# AMU-S05-V00-IsolatedCAN2.net
KiCad netlist of a schematic drawn in Altium Designer
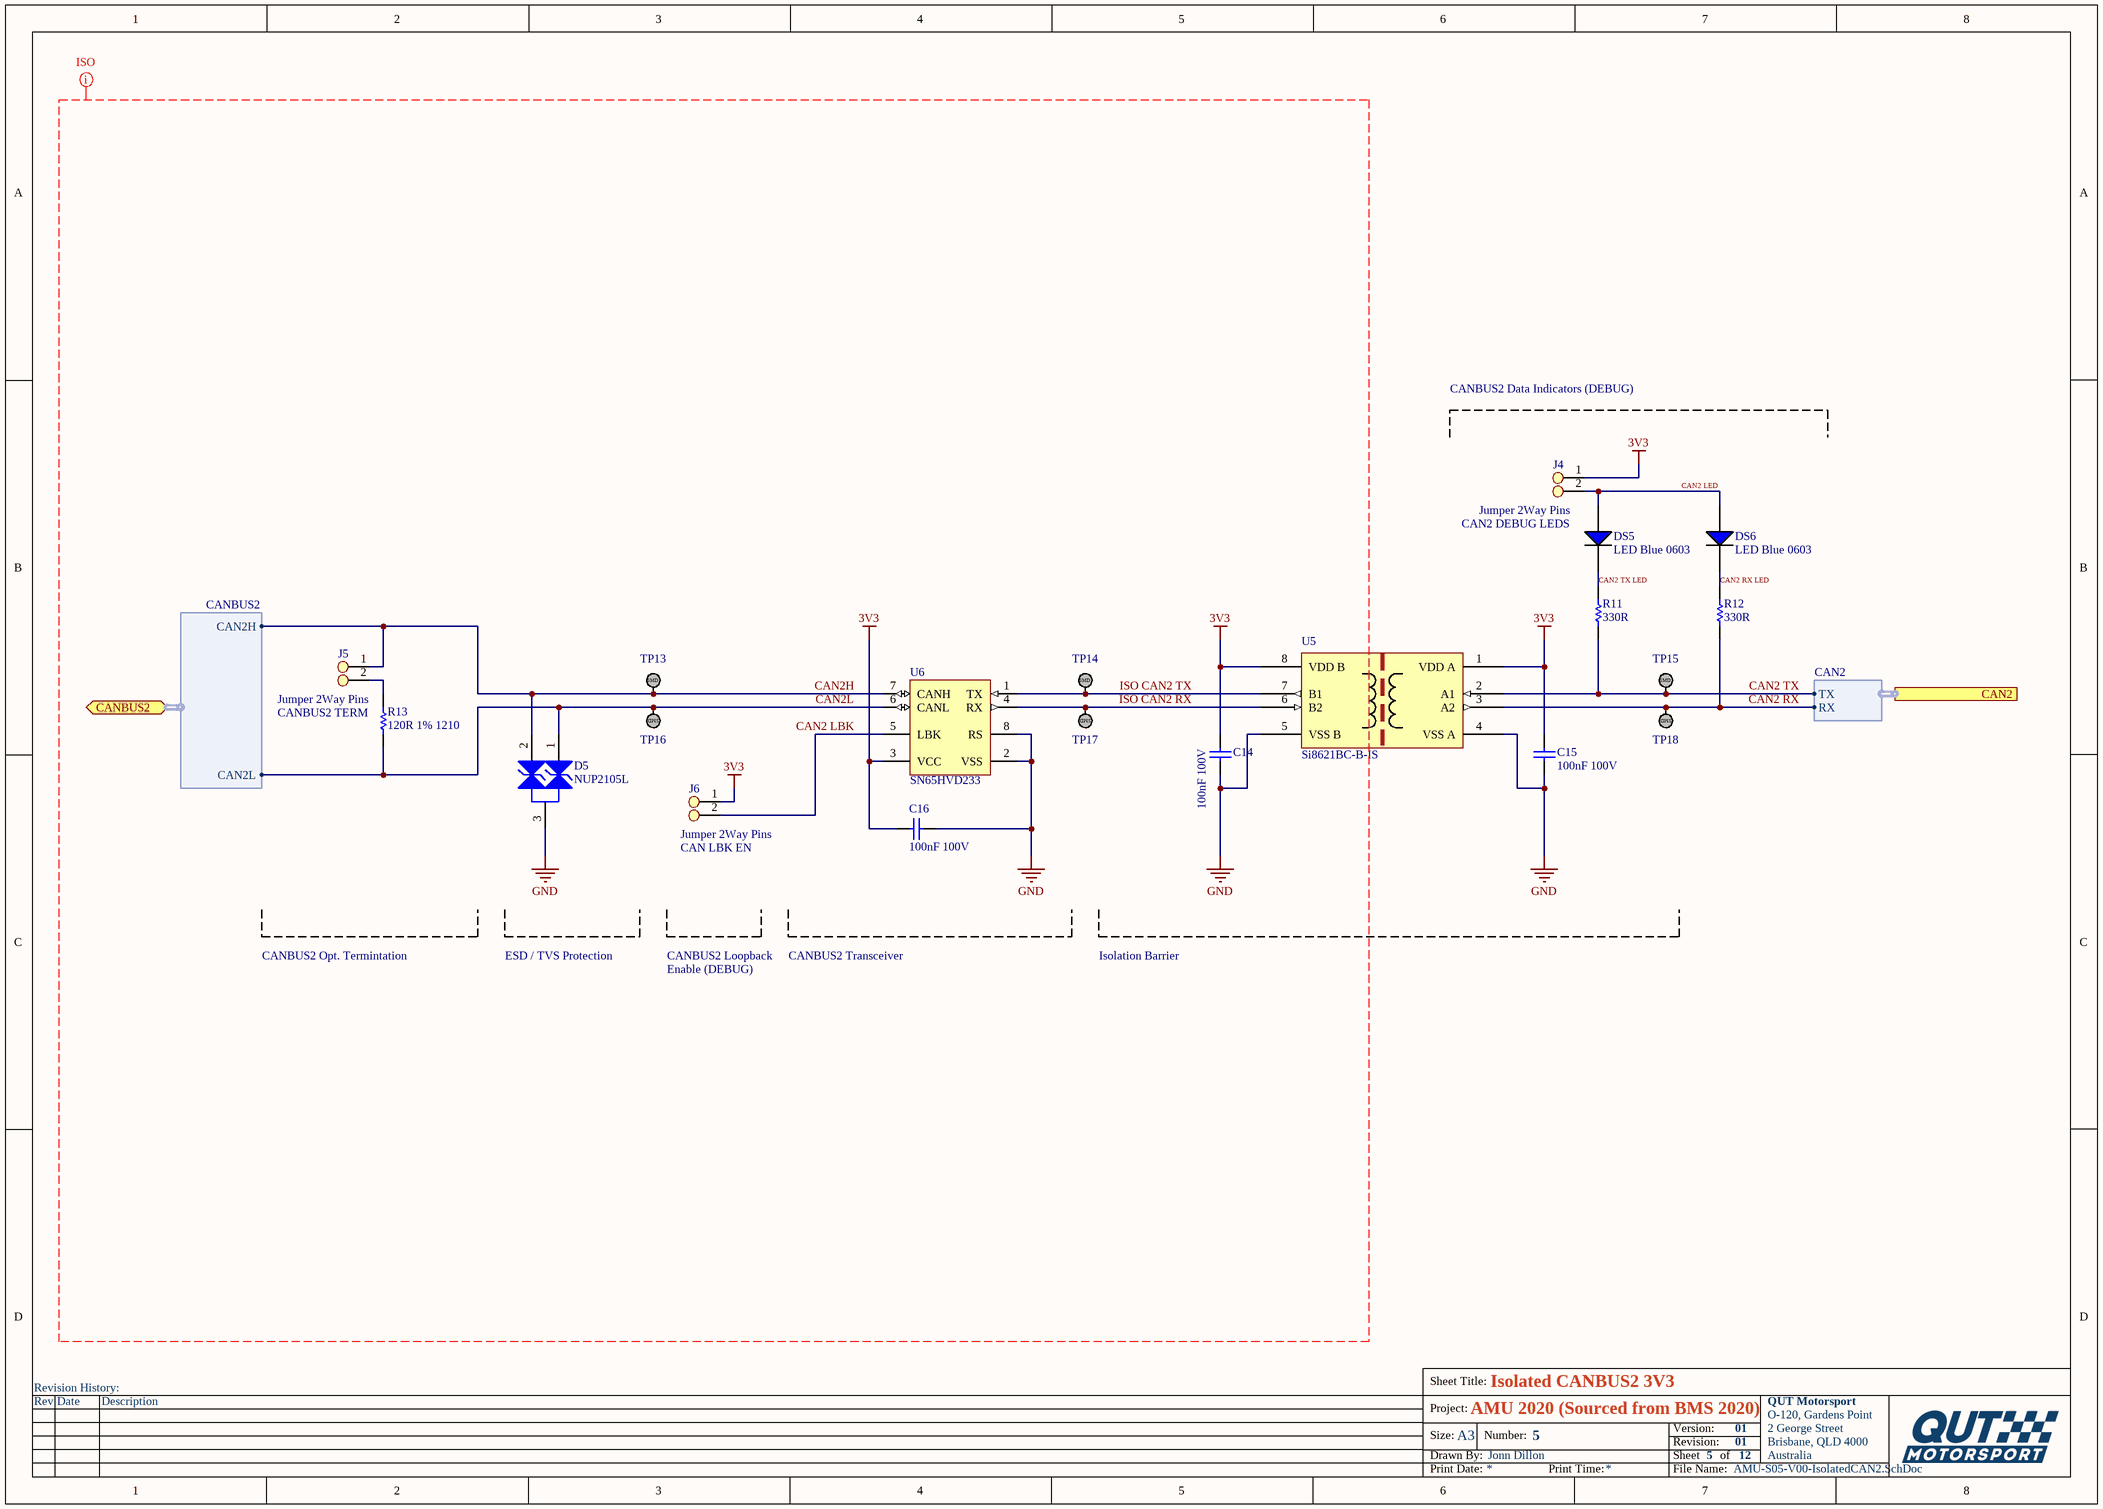
[diagram p0: AMU-S05-V00-IsolatedCAN2.SchDoc]

(export (version "E")
  (design (tool "Eeschema 10.0.6"))
  (components
    (comp (ref "C14")
      (value "100nF 100V")
      (footprint "Cap_Ceramic_0603")
      (description "Capacitor, Ceramic, SMD, 100nF, 100V, 5%, X7R, 0603")
      (libsource (lib "StandardCapacitors") (part "100nF 100V 5% X7R 0603"))
    )
    (comp (ref "C15")
      (value "100nF 100V")
      (footprint "Cap_Ceramic_0603")
      (description "Capacitor, Ceramic, SMD, 100nF, 100V, 5%, X7R, 0603")
      (libsource (lib "StandardCapacitors") (part "100nF 100V 5% X7R 0603"))
    )
    (comp (ref "C16")
      (value "100nF 100V")
      (footprint "Cap_Ceramic_0603")
      (description "Capacitor, Ceramic, SMD, 100nF, 100V, 5%, X7R, 0603")
      (libsource (lib "StandardCapacitors") (part "100nF 100V 5% X7R 0603"))
    )
    (comp (ref "D5")
      (value "NUP2105L")
      (footprint "NUP2105L")
      (libsource (lib "QUTMS_CANLibrary") (part "NUP2105L"))
    )
    (comp (ref "DS5")
      (value "LED Blue 0603")
      (footprint "LED BLUE 0603")
      (libsource (lib "QUTMS_LEDLibrary") (part "LED BLUE 0603"))
    )
    (comp (ref "DS6")
      (value "LED Blue 0603")
      (footprint "LED BLUE 0603")
      (libsource (lib "QUTMS_LEDLibrary") (part "LED BLUE 0603"))
    )
    (comp (ref "J4")
      (value "Jumper 2Way Pins")
      (footprint "Jumper_2Way_Pin")
      (description "Jumper 2Way Side Pins")
      (libsource (lib "QUTMS_JumperLibrary") (part "Jumper 2Way Side Pins"))
    )
    (comp (ref "J5")
      (value "Jumper 2Way Pins")
      (footprint "Jumper_2Way_Pin")
      (description "Jumper 2Way Side Pins")
      (libsource (lib "QUTMS_JumperLibrary") (part "Jumper 2Way Side Pins"))
    )
    (comp (ref "J6")
      (value "Jumper 2Way Pins")
      (footprint "Jumper_2Way_Pin")
      (description "Jumper 2Way Side Pins")
      (libsource (lib "QUTMS_JumperLibrary") (part "Jumper 2Way Side Pins"))
    )
    (comp (ref "R11")
      (value "330R")
      (footprint "Res_ThinFilm_0603")
      (description "Resistor, SMD, 330R, 0.1W, 5%, 0603")
      (libsource (lib "StandardResistors") (part "330R 5% 0603"))
    )
    (comp (ref "R12")
      (value "330R")
      (footprint "Res_ThinFilm_0603")
      (description "Resistor, SMD, 330R, 0.1W, 5%, 0603")
      (libsource (lib "StandardResistors") (part "330R 5% 0603"))
    )
    (comp (ref "R13")
      (value "120R 1% 1210")
      (footprint "Res_ThinFilm_1210")
      (description "Resistor, SMD, 120R, 0.25W, 1%, 1210")
      (libsource (lib "StandardResistors") (part "120R 1% 1210"))
    )
    (comp (ref "TP13")
      (value "TestPoint_SMD")
      (footprint "TestPointSMD")
      (libsource (lib "StandardTest") (part "TestPoint_SMD"))
    )
    (comp (ref "TP14")
      (value "TestPoint_SMD")
      (footprint "TestPointSMD")
      (libsource (lib "StandardTest") (part "TestPoint_SMD"))
    )
    (comp (ref "TP15")
      (value "TestPoint_SMD")
      (footprint "TestPointSMD")
      (libsource (lib "StandardTest") (part "TestPoint_SMD"))
    )
    (comp (ref "TP16")
      (value "TestPoint_SMD")
      (footprint "TestPointSMD")
      (libsource (lib "StandardTest") (part "TestPoint_SMD"))
    )
    (comp (ref "TP17")
      (value "TestPoint_SMD")
      (footprint "TestPointSMD")
      (libsource (lib "StandardTest") (part "TestPoint_SMD"))
    )
    (comp (ref "TP18")
      (value "TestPoint_SMD")
      (footprint "TestPointSMD")
      (libsource (lib "StandardTest") (part "TestPoint_SMD"))
    )
    (comp (ref "U5")
      (value "Si8621BC-B-IS")
      (footprint "Si8621BC-B-IS")
      (libsource (lib "QUTMS_IsolatorLibrary") (part "Si8621BC-B-IS"))
    )
    (comp (ref "U6")
      (value "SN65HVD233")
      (footprint "SN65HVD233DR")
      (libsource (lib "QUTMS_CANLibrary") (part "SN65HVD233"))
    )
  )
  (nets
    (net (code "3") (name "/CAN2 LBK") (class "Default")
      (node (ref "J6") (pin "2") (pinfunction "2_2") (pintype "passive"))
      (node (ref "U6") (pin "5") (pinfunction "LBK_5") (pintype "passive"))
    )
    (net (code "4") (name "/CAN2 LED") (class "Default")
      (node (ref "DS5") (pin "1") (pinfunction "A_1") (pintype "passive"))
      (node (ref "DS6") (pin "1") (pinfunction "A_1") (pintype "passive"))
      (node (ref "J4") (pin "2") (pinfunction "2_2") (pintype "passive"))
    )
    (net (code "5") (name "/CAN2 RX") (class "Default")
      (node (ref "R12") (pin "1") (pinfunction "1_1") (pintype "passive"))
      (node (ref "TP18") (pin "1") (pinfunction "1_1") (pintype "passive"))
      (node (ref "U5") (pin "3") (pinfunction "A2_3") (pintype "output"))
    )
    (net (code "6") (name "/CAN2 RX LED") (class "Default")
      (node (ref "DS6") (pin "2") (pinfunction "C_2") (pintype "passive"))
      (node (ref "R12") (pin "2") (pinfunction "2_2") (pintype "passive"))
    )
    (net (code "7") (name "/CAN2 TX") (class "Default")
      (node (ref "R11") (pin "1") (pinfunction "1_1") (pintype "passive"))
      (node (ref "TP15") (pin "1") (pinfunction "1_1") (pintype "passive"))
      (node (ref "U5") (pin "2") (pinfunction "A1_2") (pintype "input"))
    )
    (net (code "8") (name "/CAN2 TX LED") (class "Default")
      (node (ref "DS5") (pin "2") (pinfunction "C_2") (pintype "passive"))
      (node (ref "R11") (pin "2") (pinfunction "2_2") (pintype "passive"))
    )
    (net (code "9") (name "/CAN2H") (class "Default")
      (node (ref "D5") (pin "2") (pinfunction "2_2") (pintype "passive"))
      (node (ref "J5") (pin "1") (pinfunction "1_1") (pintype "passive"))
      (node (ref "TP13") (pin "1") (pinfunction "1_1") (pintype "passive"))
      (node (ref "U6") (pin "7") (pinfunction "CANH_7") (pintype "bidirectional"))
    )
    (net (code "10") (name "/CAN2L") (class "Default")
      (node (ref "D5") (pin "1") (pinfunction "1_1") (pintype "passive"))
      (node (ref "R13") (pin "1") (pinfunction "1_1") (pintype "passive"))
      (node (ref "TP16") (pin "1") (pinfunction "1_1") (pintype "passive"))
      (node (ref "U6") (pin "6") (pinfunction "CANL_6") (pintype "bidirectional"))
    )
    (net (code "11") (name "/ISO CAN2 RX") (class "Default")
      (node (ref "TP17") (pin "1") (pinfunction "1_1") (pintype "passive"))
      (node (ref "U5") (pin "6") (pinfunction "B2_6") (pintype "input"))
      (node (ref "U6") (pin "4") (pinfunction "RX_4") (pintype "output"))
    )
    (net (code "12") (name "/ISO CAN2 TX") (class "Default")
      (node (ref "TP14") (pin "1") (pinfunction "1_1") (pintype "passive"))
      (node (ref "U5") (pin "7") (pinfunction "B1_7") (pintype "output"))
      (node (ref "U6") (pin "1") (pinfunction "TX_1") (pintype "input"))
    )
    (net (code "15") (name "3V3") (class "Default")
      (node (ref "C14") (pin "2") (pinfunction "2_2") (pintype "passive"))
      (node (ref "C15") (pin "2") (pinfunction "2_2") (pintype "passive"))
      (node (ref "C16") (pin "2") (pinfunction "2_2") (pintype "passive"))
      (node (ref "J4") (pin "1") (pinfunction "1_1") (pintype "passive"))
      (node (ref "J6") (pin "1") (pinfunction "1_1") (pintype "passive"))
      (node (ref "U5") (pin "1") (pinfunction "VDD_A_1") (pintype "passive"))
      (node (ref "U5") (pin "8") (pinfunction "VDD_B_8") (pintype "passive"))
      (node (ref "U6") (pin "3") (pinfunction "VCC_3") (pintype "passive"))
    )
    (net (code "16") (name "GND") (class "Default")
      (node (ref "C14") (pin "1") (pinfunction "1_1") (pintype "passive"))
      (node (ref "C15") (pin "1") (pinfunction "1_1") (pintype "passive"))
      (node (ref "C16") (pin "1") (pinfunction "1_1") (pintype "passive"))
      (node (ref "D5") (pin "3") (pinfunction "3_3") (pintype "passive"))
      (node (ref "U5") (pin "4") (pinfunction "VSS_A_4") (pintype "passive"))
      (node (ref "U5") (pin "5") (pinfunction "VSS_B_5") (pintype "passive"))
      (node (ref "U6") (pin "2") (pinfunction "VSS_2") (pintype "passive"))
      (node (ref "U6") (pin "8") (pinfunction "RS_8") (pintype "passive"))
    )
    (net (code "17") (name "Net-(J5-Pad2)") (class "Default")
      (node (ref "J5") (pin "2") (pinfunction "2_2") (pintype "passive"))
      (node (ref "R13") (pin "2") (pinfunction "2_2") (pintype "passive"))
    )
  )
)
